# Current.net
KiCad netlist of a schematic drawn in EAGLE
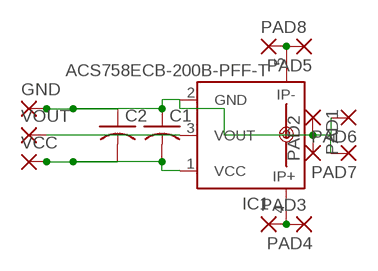
[diagram p0: schematic, sheet 1]

(export (version "E")
  (design (tool "Eeschema 10.0.6"))
  (components
    (comp (ref "C1")
      (value "C-USC0805K")
      (footprint "eagle-import:C0805K")
      (libsource (lib "eagle-import") (part "C-USC0805K"))
    )
    (comp (ref "C2")
      (value "C-USC0805K")
      (footprint "eagle-import:C0805K")
      (libsource (lib "eagle-import") (part "C-USC0805K"))
    )
    (comp (ref "GND")
      (value "SMD2")
      (footprint "eagle-import:SMD1,27-2,54")
      (libsource (lib "eagle-import") (part "SMD2"))
    )
    (comp (ref "IC1")
      (value "ACS758ECB-200B-PFF-T")
      (footprint "eagle-import:CB-PFF")
      (libsource (lib "eagle-import") (part "ACS758ECB-200B-PFF-T"))
    )
    (comp (ref "PAD1")
      (value "SMD5")
      (footprint "eagle-import:SMD2,54-5,08")
      (libsource (lib "eagle-import") (part "SMD5"))
    )
    (comp (ref "PAD2")
      (value "SMD5")
      (footprint "eagle-import:SMD2,54-5,08")
      (libsource (lib "eagle-import") (part "SMD5"))
    )
    (comp (ref "PAD3")
      (value "SMD5")
      (footprint "eagle-import:SMD2,54-5,08")
      (libsource (lib "eagle-import") (part "SMD5"))
    )
    (comp (ref "PAD4")
      (value "SMD5")
      (footprint "eagle-import:SMD2,54-5,08")
      (libsource (lib "eagle-import") (part "SMD5"))
    )
    (comp (ref "PAD5")
      (value "SMD5")
      (footprint "eagle-import:SMD2,54-5,08")
      (libsource (lib "eagle-import") (part "SMD5"))
    )
    (comp (ref "PAD6")
      (value "SMD5")
      (footprint "eagle-import:SMD2,54-5,08")
      (libsource (lib "eagle-import") (part "SMD5"))
    )
    (comp (ref "PAD7")
      (value "SMD5")
      (footprint "eagle-import:SMD2,54-5,08")
      (libsource (lib "eagle-import") (part "SMD5"))
    )
    (comp (ref "PAD8")
      (value "SMD5")
      (footprint "eagle-import:SMD2,54-5,08")
      (libsource (lib "eagle-import") (part "SMD5"))
    )
    (comp (ref "VCC")
      (value "SMD2")
      (footprint "eagle-import:SMD1,27-2,54")
      (libsource (lib "eagle-import") (part "SMD2"))
    )
    (comp (ref "VOUT")
      (value "SMD2")
      (footprint "eagle-import:SMD1,27-2,54")
      (libsource (lib "eagle-import") (part "SMD2"))
    )
  )
  (nets
    (net (code "1") (name "Net-(GND-P)") (class "Default")
      (node (ref "C1") (pin "1") (pinfunction "1_1") (pintype "passive"))
      (node (ref "C2") (pin "1") (pinfunction "1_1") (pintype "passive"))
      (node (ref "GND") (pin "1") (pinfunction "P_1") (pintype "passive"))
      (node (ref "IC1") (pin "2") (pinfunction "GND_2") (pintype "power_in"))
      (node (ref "PAD1") (pin "1") (pinfunction "P_1") (pintype "passive"))
      (node (ref "PAD2") (pin "1") (pinfunction "P_1") (pintype "passive"))
      (node (ref "PAD6") (pin "1") (pinfunction "P_1") (pintype "passive"))
      (node (ref "PAD7") (pin "1") (pinfunction "P_1") (pintype "passive"))
    )
    (net (code "2") (name "Net-(IC1-IP+)") (class "Default")
      (node (ref "IC1") (pin "4") (pinfunction "IP+_4") (pintype "passive"))
      (node (ref "PAD3") (pin "1") (pinfunction "P_1") (pintype "passive"))
      (node (ref "PAD4") (pin "1") (pinfunction "P_1") (pintype "passive"))
    )
    (net (code "3") (name "Net-(IC1-IP-)") (class "Default")
      (node (ref "IC1") (pin "5") (pinfunction "IP-_5") (pintype "passive"))
      (node (ref "PAD5") (pin "1") (pinfunction "P_1") (pintype "passive"))
      (node (ref "PAD8") (pin "1") (pinfunction "P_1") (pintype "passive"))
    )
    (net (code "4") (name "Net-(IC1-VCC)") (class "Default")
      (node (ref "C1") (pin "2") (pinfunction "2_2") (pintype "passive"))
      (node (ref "C2") (pin "2") (pinfunction "2_2") (pintype "passive"))
      (node (ref "IC1") (pin "1") (pinfunction "VCC_1") (pintype "power_in"))
      (node (ref "VCC") (pin "1") (pinfunction "P_1") (pintype "passive"))
    )
    (net (code "5") (name "Net-(IC1-VOUT)") (class "Default")
      (node (ref "IC1") (pin "3") (pinfunction "VOUT_3") (pintype "output"))
      (node (ref "VOUT") (pin "1") (pinfunction "P_1") (pintype "passive"))
    )
    (net (code "6") (name "unconnected-(IC1-PadIP+1)") (class "Default")
      (node (ref "IC1") (pin "IP+1") (pinfunction "IP+1_IP+1") (pintype "input"))
    )
    (net (code "7") (name "unconnected-(IC1-PadIP-1)") (class "Default")
      (node (ref "IC1") (pin "IP-1") (pinfunction "IP-1_IP-1") (pintype "input"))
    )
  )
)
